# opaq_n3.net
KiCad netlist of a schematic drawn in EAGLE
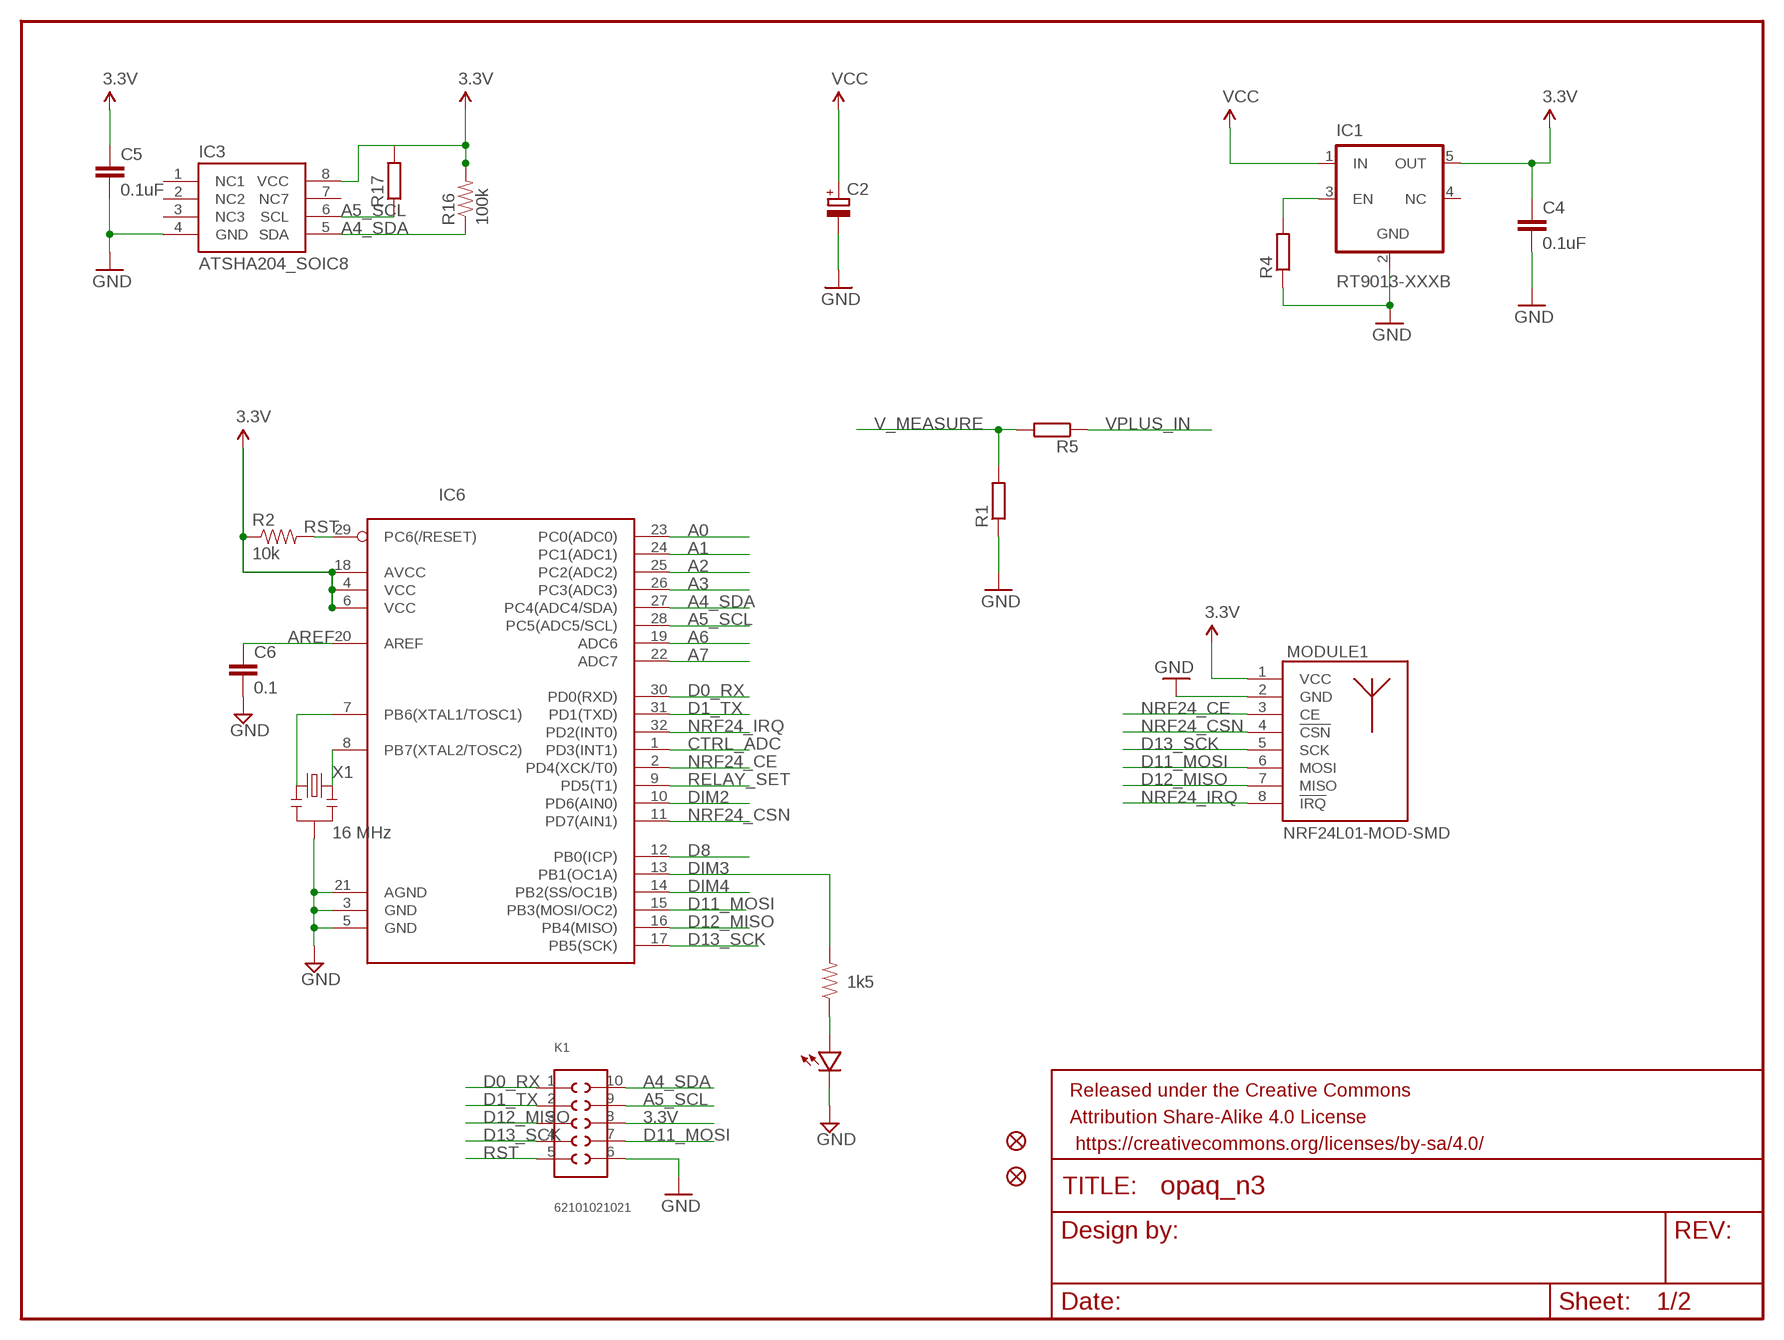
[diagram p0: schematic, sheet 1]
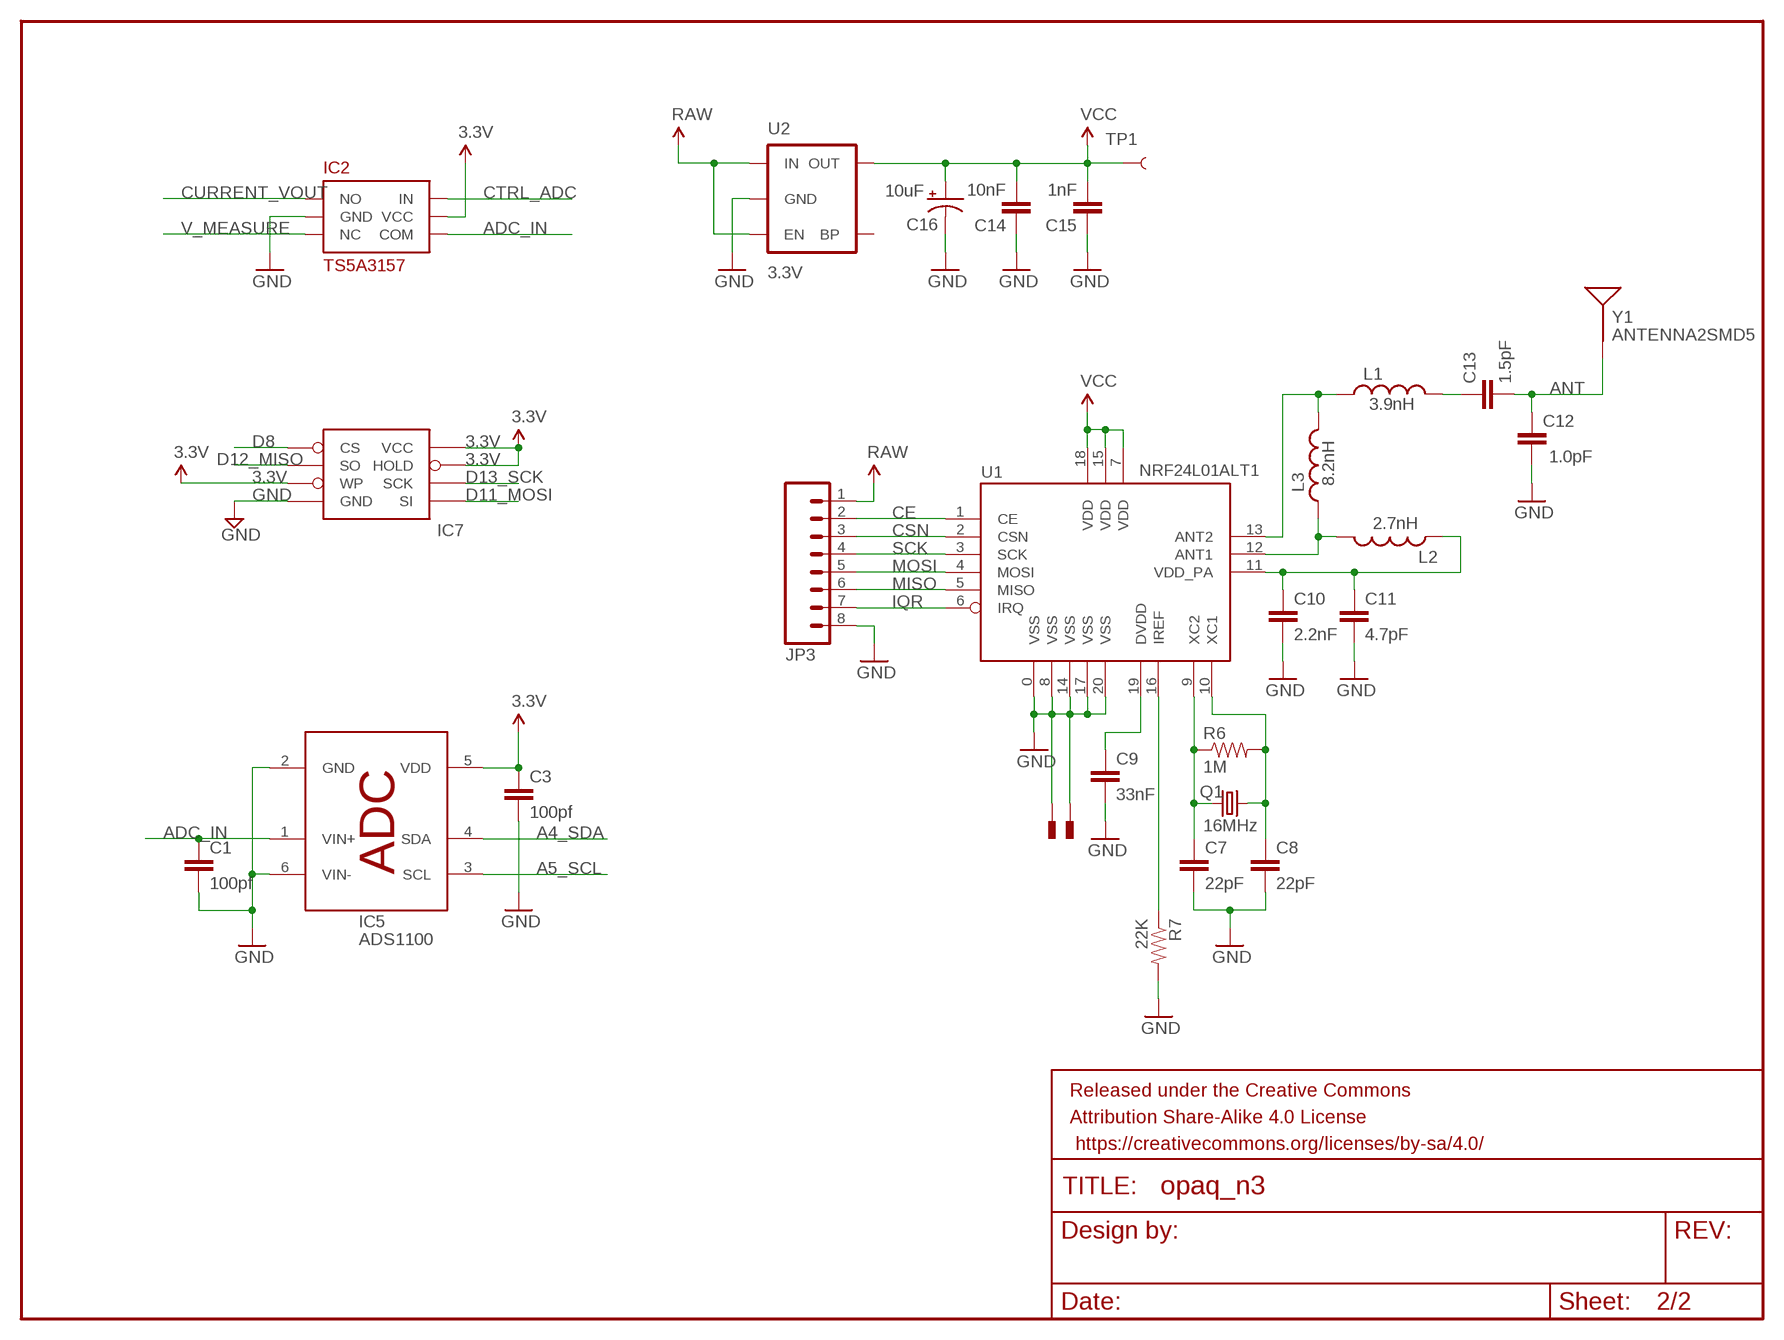
[diagram p1: schematic, sheet 2]

(export (version "E")
  (design (tool "Eeschema 10.0.6"))
  (components
    (comp (ref "C2")
      (value "CPOL-EUC/6032-28R")
      (footprint "eagle-import:C_6032-28R")
      (libsource (lib "eagle-import") (part "CPOL-EUC/6032-28R"))
    )
    (comp (ref "C4")
      (value "0.1uF")
      (footprint "eagle-import:0805")
      (libsource (lib "eagle-import") (part "SparkFun-Passives_CAP0805"))
    )
    (comp (ref "C5")
      (value "0.1uF")
      (footprint "eagle-import:0805")
      (libsource (lib "eagle-import") (part "SparkFun-Passives_CAP0805"))
    )
    (comp (ref "C6")
      (value "0.1")
      (footprint "eagle-import:0603-CAP")
      (libsource (lib "eagle-import") (part "CAP0603-CAP"))
    )
    (comp (ref "DIM")
      (value "LED0603")
      (footprint "eagle-import:0603-LED")
      (libsource (lib "eagle-import") (part "LED0603"))
    )
    (comp (ref "FRAME1")
      (value "FRAME-LETTER")
      (footprint "eagle-import:CREATIVE_COMMONS")
      (libsource (lib "eagle-import") (part "FRAME-LETTER"))
    )
    (comp (ref "IC1")
      (value "RT9013-XXXB")
      (footprint "eagle-import:SOT23-5")
      (libsource (lib "eagle-import") (part "RT9013-XXXB"))
    )
    (comp (ref "IC3")
      (value "ATSHA204_SOIC8")
      (footprint "eagle-import:SOIC8")
      (libsource (lib "eagle-import") (part "ATSHA204_SOIC8"))
    )
    (comp (ref "IC6")
      (value "ATMega-328")
      (footprint "eagle-import:MLF32")
      (libsource (lib "eagle-import") (part "ATMEGA168/328MLF"))
    )
    (comp (ref "JP1")
      (value "FIDUCIAL1X2.5")
      (footprint "eagle-import:FIDUCIAL-1X2.5")
      (libsource (lib "eagle-import") (part "FIDUCIAL1X2.5"))
    )
    (comp (ref "JP2")
      (value "FIDUCIAL1X2.5")
      (footprint "eagle-import:FIDUCIAL-1X2.5")
      (libsource (lib "eagle-import") (part "FIDUCIAL1X2.5"))
    )
    (comp (ref "K1")
      (value "62101021021")
      (footprint "eagle-import:62101021021")
      (libsource (lib "eagle-import") (part "62101021021"))
    )
    (comp (ref "MODULE1")
      (value "NRF24L01-MOD-SMD")
      (footprint "eagle-import:SMD8-MODULE")
      (libsource (lib "eagle-import") (part "NRF24L01-MOD-SMD"))
    )
    (comp (ref "R1")
      (value "R-EU_R0805")
      (footprint "eagle-import:0805")
      (libsource (lib "eagle-import") (part "R-EU_R0805"))
    )
    (comp (ref "R2")
      (value "10k")
      (footprint "eagle-import:0603-RES")
      (libsource (lib "eagle-import") (part "RESISTOR0603-RES"))
    )
    (comp (ref "R3")
      (value "1k5")
      (footprint "eagle-import:0603-RES")
      (libsource (lib "eagle-import") (part "RESISTOR0603-RES"))
    )
    (comp (ref "R4")
      (value "R-EU_R0805")
      (footprint "eagle-import:0805")
      (libsource (lib "eagle-import") (part "R-EU_R0805"))
    )
    (comp (ref "R5")
      (value "R-EU_R0805")
      (footprint "eagle-import:0805")
      (libsource (lib "eagle-import") (part "R-EU_R0805"))
    )
    (comp (ref "R16")
      (value "100k")
      (footprint "eagle-import:0805")
      (libsource (lib "eagle-import") (part "SparkFun-Passives_RESISTOR0805-RES"))
    )
    (comp (ref "R17")
      (value "R-EU_R0805")
      (footprint "eagle-import:0805")
      (libsource (lib "eagle-import") (part "R-EU_R0805"))
    )
    (comp (ref "X1")
      (value "16 MHz")
      (footprint "eagle-import:RESONATOR-SMD")
      (libsource (lib "eagle-import") (part "RESONATORSMD"))
    )
    (comp (ref "C1")
      (value "100pf")
      (footprint "eagle-import:0402-CAP")
      (libsource (lib "eagle-import") (part "SparkFun-Passives_CAP0402-CAP"))
    )
    (comp (ref "C3")
      (value "100pf")
      (footprint "eagle-import:0402-CAP")
      (libsource (lib "eagle-import") (part "SparkFun-Passives_CAP0402-CAP"))
    )
    (comp (ref "C7")
      (value "22pF")
      (footprint "eagle-import:0402-CAP")
      (libsource (lib "eagle-import") (part "SparkFun_CAP0402-CAP"))
    )
    (comp (ref "C8")
      (value "22pF")
      (footprint "eagle-import:0402-CAP")
      (libsource (lib "eagle-import") (part "SparkFun_CAP0402-CAP"))
    )
    (comp (ref "C9")
      (value "33nF")
      (footprint "eagle-import:0402-CAP")
      (libsource (lib "eagle-import") (part "SparkFun_CAP0402-CAP"))
    )
    (comp (ref "C10")
      (value "2.2nF")
      (footprint "eagle-import:0402-CAP")
      (libsource (lib "eagle-import") (part "SparkFun_CAP0402-CAP"))
    )
    (comp (ref "C11")
      (value "4.7pF")
      (footprint "eagle-import:0402-CAP")
      (libsource (lib "eagle-import") (part "SparkFun_CAP0402-CAP"))
    )
    (comp (ref "C12")
      (value "1.0pF")
      (footprint "eagle-import:0402-CAP")
      (libsource (lib "eagle-import") (part "SparkFun_CAP0402-CAP"))
    )
    (comp (ref "C13")
      (value "1.5pF")
      (footprint "eagle-import:0402-CAP")
      (libsource (lib "eagle-import") (part "SparkFun_CAP0402-CAP"))
    )
    (comp (ref "C14")
      (value "10nF")
      (footprint "eagle-import:0402-CAP")
      (libsource (lib "eagle-import") (part "SparkFun_CAP0402-CAP"))
    )
    (comp (ref "C15")
      (value "1nF")
      (footprint "eagle-import:0402-CAP")
      (libsource (lib "eagle-import") (part "SparkFun_CAP0402-CAP"))
    )
    (comp (ref "C16")
      (value "10uF")
      (footprint "eagle-import:EIA3216")
      (libsource (lib "eagle-import") (part "CAP_POL1206"))
    )
    (comp (ref "FRAME2")
      (value "FRAME-LETTERNO_PACKAGE")
      (footprint "eagle-import:DUMMY")
      (fields (field (name "DESIGNER") "Nobody"))
      (libsource (lib "eagle-import") (part "FRAME-LETTERNO_PACKAGE"))
    )
    (comp (ref "IC2")
      (value "TS5A3157")
      (footprint "eagle-import:SOT23-6")
      (libsource (lib "eagle-import") (part "TS5A3157"))
    )
    (comp (ref "IC5")
      (value "ADS1100")
      (footprint "eagle-import:SOT23-6")
      (fields (field (name "MF") "TI"))
      (libsource (lib "eagle-import") (part "ADS1100"))
    )
    (comp (ref "IC7")
      (value "AT25F512BWIDE_5.3MM")
      (footprint "eagle-import:SO08WIDE")
      (libsource (lib "eagle-import") (part "AT25F512BWIDE_5.3MM"))
    )
    (comp (ref "JP3")
      (value "M081X08")
      (footprint "eagle-import:1X08")
      (libsource (lib "eagle-import") (part "M081X08"))
    )
    (comp (ref "L1")
      (value "3.9nH")
      (footprint "eagle-import:C0402")
      (libsource (lib "eagle-import") (part "INDUCTOR0402"))
    )
    (comp (ref "L2")
      (value "2.7nH")
      (footprint "eagle-import:C0402")
      (libsource (lib "eagle-import") (part "INDUCTOR0402"))
    )
    (comp (ref "L3")
      (value "8.2nH")
      (footprint "eagle-import:C0402")
      (libsource (lib "eagle-import") (part "INDUCTOR0402"))
    )
    (comp (ref "Q1")
      (value "16MHz")
      (footprint "eagle-import:CRYSTAL-SMD-5X3")
      (libsource (lib "eagle-import") (part "CRYSTAL5X3"))
    )
    (comp (ref "R6")
      (value "1M")
      (footprint "eagle-import:0402-RES")
      (libsource (lib "eagle-import") (part "SparkFun_RESISTOR0402-RES"))
    )
    (comp (ref "R7")
      (value "22K")
      (footprint "eagle-import:0402-RES")
      (libsource (lib "eagle-import") (part "SparkFun_RESISTOR0402-RES"))
    )
    (comp (ref "TP1")
      (value "TEST-POINT3X5")
      (footprint "eagle-import:PAD.03X.05")
      (libsource (lib "eagle-import") (part "TEST-POINT3X5"))
    )
    (comp (ref "U$1")
      (value "PAD")
      (footprint "eagle-import:PAD-0.008")
      (libsource (lib "eagle-import") (part "PAD"))
    )
    (comp (ref "U$4")
      (value "PAD")
      (footprint "eagle-import:PAD-0.008")
      (libsource (lib "eagle-import") (part "PAD"))
    )
    (comp (ref "U1")
      (value "NRF24L01ALT1")
      (footprint "eagle-import:QFN20_ALT1")
      (libsource (lib "eagle-import") (part "NRF24L01ALT1"))
    )
    (comp (ref "U2")
      (value "3.3V")
      (footprint "eagle-import:SOT23-5")
      (libsource (lib "eagle-import") (part "V_REG_LDOSMD"))
    )
    (comp (ref "Y1")
      (value "ANTENNA2SMD5")
      (footprint "eagle-import:ANTENNA-CHIP5")
      (libsource (lib "eagle-import") (part "ANTENNA2SMD5"))
    )
  )
  (nets
    (net (code "1") (name "3.3V") (class "Default")
      (node (ref "C3") (pin "1") (pinfunction "1_1") (pintype "passive"))
      (node (ref "C4") (pin "1") (pinfunction "1_1") (pintype "passive"))
      (node (ref "C5") (pin "1") (pinfunction "1_1") (pintype "passive"))
      (node (ref "IC1") (pin "5") (pinfunction "OUT_5") (pintype "passive"))
      (node (ref "IC2") (pin "5") (pinfunction "VCC_5") (pintype "bidirectional"))
      (node (ref "IC3") (pin "8") (pinfunction "VCC_8") (pintype "power_in"))
      (node (ref "IC5") (pin "5") (pinfunction "VDD_5") (pintype "power_in"))
      (node (ref "IC6") (pin "18") (pinfunction "AVCC_18") (pintype "bidirectional"))
      (node (ref "IC6") (pin "4") (pinfunction "VCC_4") (pintype "bidirectional"))
      (node (ref "IC6") (pin "6") (pinfunction "VCC_6") (pintype "bidirectional"))
      (node (ref "IC7") (pin "3") (pinfunction "WP_3") (pintype "bidirectional"))
      (node (ref "IC7") (pin "7") (pinfunction "HOLD_7") (pintype "bidirectional"))
      (node (ref "IC7") (pin "8") (pinfunction "VCC_8") (pintype "bidirectional"))
      (node (ref "K1") (pin "8") (pinfunction "8_8") (pintype "passive"))
      (node (ref "MODULE1") (pin "1") (pinfunction "VCC_1") (pintype "power_in"))
      (node (ref "R16") (pin "2") (pinfunction "2_2") (pintype "passive"))
      (node (ref "R17") (pin "2") (pinfunction "2_2") (pintype "passive"))
      (node (ref "R2") (pin "1") (pinfunction "1_1") (pintype "passive"))
    )
    (net (code "2") (name "A0") (class "Default")
      (node (ref "IC6") (pin "23") (pinfunction "PC0(ADC0)_23") (pintype "bidirectional"))
    )
    (net (code "3") (name "A1") (class "Default")
      (node (ref "IC6") (pin "24") (pinfunction "PC1(ADC1)_24") (pintype "bidirectional"))
    )
    (net (code "4") (name "A2") (class "Default")
      (node (ref "IC6") (pin "25") (pinfunction "PC2(ADC2)_25") (pintype "bidirectional"))
    )
    (net (code "5") (name "A3") (class "Default")
      (node (ref "IC6") (pin "26") (pinfunction "PC3(ADC3)_26") (pintype "bidirectional"))
    )
    (net (code "6") (name "A4_SDA") (class "Default")
      (node (ref "IC3") (pin "5") (pinfunction "SDA_5") (pintype "bidirectional"))
      (node (ref "IC5") (pin "4") (pinfunction "SDA_4") (pintype "bidirectional"))
      (node (ref "IC6") (pin "27") (pinfunction "PC4(ADC4/SDA)_27") (pintype "bidirectional"))
      (node (ref "K1") (pin "10") (pinfunction "10_10") (pintype "passive"))
      (node (ref "R16") (pin "1") (pinfunction "1_1") (pintype "passive"))
    )
    (net (code "7") (name "A5_SCL") (class "Default")
      (node (ref "IC3") (pin "6") (pinfunction "SCL_6") (pintype "bidirectional"))
      (node (ref "IC5") (pin "3") (pinfunction "SCL_3") (pintype "input"))
      (node (ref "IC6") (pin "28") (pinfunction "PC5(ADC5/SCL)_28") (pintype "bidirectional"))
      (node (ref "K1") (pin "9") (pinfunction "9_9") (pintype "passive"))
      (node (ref "R17") (pin "1") (pinfunction "1_1") (pintype "passive"))
    )
    (net (code "8") (name "A6") (class "Default")
      (node (ref "IC6") (pin "19") (pinfunction "ADC6_19") (pintype "bidirectional"))
    )
    (net (code "9") (name "A7") (class "Default")
      (node (ref "IC6") (pin "22") (pinfunction "ADC7_22") (pintype "bidirectional"))
    )
    (net (code "10") (name "ADC_IN") (class "Default")
      (node (ref "C1") (pin "1") (pinfunction "1_1") (pintype "passive"))
      (node (ref "IC2") (pin "4") (pinfunction "COM_4") (pintype "bidirectional"))
      (node (ref "IC5") (pin "1") (pinfunction "VIN+_1") (pintype "input"))
    )
    (net (code "11") (name "ANT") (class "Default")
      (node (ref "C12") (pin "2") (pinfunction "2_2") (pintype "passive"))
      (node (ref "C13") (pin "2") (pinfunction "2_2") (pintype "passive"))
      (node (ref "Y1") (pin "FEED") (pinfunction "SIGNAL_FEED") (pintype "bidirectional"))
    )
    (net (code "12") (name "AREF") (class "Default")
      (node (ref "C6") (pin "1") (pinfunction "1_1") (pintype "passive"))
      (node (ref "IC6") (pin "20") (pinfunction "AREF_20") (pintype "bidirectional"))
    )
    (net (code "13") (name "CE") (class "Default")
      (node (ref "JP3") (pin "2") (pinfunction "2_2") (pintype "passive"))
      (node (ref "U1") (pin "1") (pinfunction "CE_1") (pintype "input"))
    )
    (net (code "14") (name "CSN") (class "Default")
      (node (ref "JP3") (pin "3") (pinfunction "3_3") (pintype "passive"))
      (node (ref "U1") (pin "2") (pinfunction "CSN_2") (pintype "input"))
    )
    (net (code "15") (name "CTRL_ADC") (class "Default")
      (node (ref "IC2") (pin "6") (pinfunction "IN_6") (pintype "bidirectional"))
      (node (ref "IC6") (pin "1") (pinfunction "PD3(INT1)_1") (pintype "bidirectional"))
    )
    (net (code "16") (name "CURRENT_VOUT") (class "Default")
      (node (ref "IC2") (pin "1") (pinfunction "NO_1") (pintype "bidirectional"))
    )
    (net (code "17") (name "D0_RX") (class "Default")
      (node (ref "IC6") (pin "30") (pinfunction "PD0(RXD)_30") (pintype "bidirectional"))
      (node (ref "K1") (pin "1") (pinfunction "1_1") (pintype "passive"))
    )
    (net (code "18") (name "D1_TX") (class "Default")
      (node (ref "IC6") (pin "31") (pinfunction "PD1(TXD)_31") (pintype "bidirectional"))
      (node (ref "K1") (pin "2") (pinfunction "2_2") (pintype "passive"))
    )
    (net (code "19") (name "D8") (class "Default")
      (node (ref "IC6") (pin "12") (pinfunction "PB0(ICP)_12") (pintype "bidirectional"))
      (node (ref "IC7") (pin "1") (pinfunction "CS_1") (pintype "bidirectional"))
    )
    (net (code "20") (name "D11_MOSI") (class "Default")
      (node (ref "IC6") (pin "15") (pinfunction "PB3(MOSI/OC2)_15") (pintype "bidirectional"))
      (node (ref "IC7") (pin "5") (pinfunction "SI_5") (pintype "bidirectional"))
      (node (ref "K1") (pin "7") (pinfunction "7_7") (pintype "passive"))
      (node (ref "MODULE1") (pin "6") (pinfunction "MOSI_6") (pintype "input"))
    )
    (net (code "21") (name "D12_MISO") (class "Default")
      (node (ref "IC6") (pin "16") (pinfunction "PB4(MISO)_16") (pintype "bidirectional"))
      (node (ref "IC7") (pin "2") (pinfunction "SO_2") (pintype "bidirectional"))
      (node (ref "K1") (pin "3") (pinfunction "3_3") (pintype "passive"))
      (node (ref "MODULE1") (pin "7") (pinfunction "MISO_7") (pintype "output"))
    )
    (net (code "22") (name "D13_SCK") (class "Default")
      (node (ref "IC6") (pin "17") (pinfunction "PB5(SCK)_17") (pintype "bidirectional"))
      (node (ref "IC7") (pin "6") (pinfunction "SCK_6") (pintype "bidirectional"))
      (node (ref "K1") (pin "4") (pinfunction "4_4") (pintype "passive"))
      (node (ref "MODULE1") (pin "5") (pinfunction "SCK_5") (pintype "input"))
    )
    (net (code "23") (name "DIM2") (class "Default")
      (node (ref "IC6") (pin "10") (pinfunction "PD6(AIN0)_10") (pintype "bidirectional"))
    )
    (net (code "24") (name "DIM3") (class "Default")
      (node (ref "IC6") (pin "13") (pinfunction "PB1(OC1A)_13") (pintype "bidirectional"))
      (node (ref "R3") (pin "2") (pinfunction "2_2") (pintype "passive"))
    )
    (net (code "25") (name "DIM4") (class "Default")
      (node (ref "IC6") (pin "14") (pinfunction "PB2(SS/OC1B)_14") (pintype "bidirectional"))
    )
    (net (code "26") (name "GND") (class "Default")
      (node (ref "C1") (pin "2") (pinfunction "2_2") (pintype "passive"))
      (node (ref "C10") (pin "2") (pinfunction "2_2") (pintype "passive"))
      (node (ref "C11") (pin "2") (pinfunction "2_2") (pintype "passive"))
      (node (ref "C12") (pin "1") (pinfunction "1_1") (pintype "passive"))
      (node (ref "C14") (pin "1") (pinfunction "1_1") (pintype "passive"))
      (node (ref "C15") (pin "1") (pinfunction "1_1") (pintype "passive"))
      (node (ref "C16") (pin "C") (pinfunction "-_C") (pintype "passive"))
      (node (ref "C2") (pin "-") (pinfunction "-_-") (pintype "passive"))
      (node (ref "C3") (pin "2") (pinfunction "2_2") (pintype "passive"))
      (node (ref "C4") (pin "2") (pinfunction "2_2") (pintype "passive"))
      (node (ref "C5") (pin "2") (pinfunction "2_2") (pintype "passive"))
      (node (ref "C6") (pin "2") (pinfunction "2_2") (pintype "passive"))
      (node (ref "C7") (pin "2") (pinfunction "2_2") (pintype "passive"))
      (node (ref "C8") (pin "2") (pinfunction "2_2") (pintype "passive"))
      (node (ref "C9") (pin "2") (pinfunction "2_2") (pintype "passive"))
      (node (ref "DIM") (pin "MINUS") (pinfunction "MINUS_MINUS") (pintype "passive"))
      (node (ref "IC1") (pin "2") (pinfunction "GND_2") (pintype "power_in"))
      (node (ref "IC2") (pin "2") (pinfunction "GND_2") (pintype "bidirectional"))
      (node (ref "IC3") (pin "4") (pinfunction "GND_4") (pintype "power_in"))
      (node (ref "IC5") (pin "2") (pinfunction "GND_2") (pintype "power_in"))
      (node (ref "IC5") (pin "6") (pinfunction "VIN-_6") (pintype "input"))
      (node (ref "IC6") (pin "21") (pinfunction "AGND_21") (pintype "bidirectional"))
      (node (ref "IC6") (pin "3") (pinfunction "GND_3") (pintype "bidirectional"))
      (node (ref "IC6") (pin "5") (pinfunction "GND_5") (pintype "bidirectional"))
      (node (ref "IC7") (pin "4") (pinfunction "GND_4") (pintype "bidirectional"))
      (node (ref "JP3") (pin "8") (pinfunction "8_8") (pintype "passive"))
      (node (ref "K1") (pin "6") (pinfunction "6_6") (pintype "passive"))
      (node (ref "MODULE1") (pin "2") (pinfunction "GND_2") (pintype "power_in"))
      (node (ref "R1") (pin "1") (pinfunction "1_1") (pintype "passive"))
      (node (ref "R4") (pin "1") (pinfunction "1_1") (pintype "passive"))
      (node (ref "R7") (pin "2") (pinfunction "2_2") (pintype "passive"))
      (node (ref "U$1") (pin "P$1") (pinfunction "P$1_P$1") (pintype "bidirectional"))
      (node (ref "U$4") (pin "P$1") (pinfunction "P$1_P$1") (pintype "bidirectional"))
      (node (ref "U1") (pin "0") (pinfunction "VSS_0") (pintype "power_in"))
      (node (ref "U1") (pin "14") (pinfunction "VSS_14") (pintype "power_in"))
      (node (ref "U1") (pin "17") (pinfunction "VSS_17") (pintype "power_in"))
      (node (ref "U1") (pin "20") (pinfunction "VSS_20") (pintype "power_in"))
      (node (ref "U1") (pin "8") (pinfunction "VSS_8") (pintype "power_in"))
      (node (ref "U2") (pin "2") (pinfunction "GND_2") (pintype "input"))
      (node (ref "X1") (pin "2") (pinfunction "2_2") (pintype "passive"))
    )
    (net (code "27") (name "IQR") (class "Default")
      (node (ref "JP3") (pin "7") (pinfunction "7_7") (pintype "passive"))
      (node (ref "U1") (pin "6") (pinfunction "IRQ_6") (pintype "output"))
    )
    (net (code "28") (name "MISO") (class "Default")
      (node (ref "JP3") (pin "6") (pinfunction "6_6") (pintype "passive"))
      (node (ref "U1") (pin "5") (pinfunction "MISO_5") (pintype "output"))
    )
    (net (code "29") (name "MOSI") (class "Default")
      (node (ref "JP3") (pin "5") (pinfunction "5_5") (pintype "passive"))
      (node (ref "U1") (pin "4") (pinfunction "MOSI_4") (pintype "input"))
    )
    (net (code "30") (name "NRF24_CE") (class "Default")
      (node (ref "IC6") (pin "2") (pinfunction "PD4(XCK/T0)_2") (pintype "bidirectional"))
      (node (ref "MODULE1") (pin "3") (pinfunction "CE_3") (pintype "input"))
    )
    (net (code "31") (name "NRF24_CSN") (class "Default")
      (node (ref "IC6") (pin "11") (pinfunction "PD7(AIN1)_11") (pintype "bidirectional"))
      (node (ref "MODULE1") (pin "4") (pinfunction "~{CSN}_4") (pintype "input"))
    )
    (net (code "32") (name "NRF24_IRQ") (class "Default")
      (node (ref "IC6") (pin "32") (pinfunction "PD2(INT0)_32") (pintype "bidirectional"))
      (node (ref "MODULE1") (pin "8") (pinfunction "~{IRQ}_8") (pintype "open_collector"))
    )
    (net (code "33") (name "Net-(C13-Pad1)") (class "Default")
      (node (ref "C13") (pin "1") (pinfunction "1_1") (pintype "passive"))
      (node (ref "L1") (pin "2") (pinfunction "2_2") (pintype "passive"))
    )
    (net (code "34") (name "Net-(DIM-PadPLUS)") (class "Default")
      (node (ref "DIM") (pin "PLUS") (pinfunction "PLUS_PLUS") (pintype "passive"))
      (node (ref "R3") (pin "1") (pinfunction "1_1") (pintype "passive"))
    )
    (net (code "35") (name "Net-(IC1-EN)") (class "Default")
      (node (ref "IC1") (pin "3") (pinfunction "EN_3") (pintype "input"))
      (node (ref "R4") (pin "2") (pinfunction "2_2") (pintype "passive"))
    )
    (net (code "36") (name "Net-(IC6-PB6(XTAL1{slash}TOSC1))") (class "Default")
      (node (ref "IC6") (pin "7") (pinfunction "PB6(XTAL1/TOSC1)_7") (pintype "bidirectional"))
      (node (ref "X1") (pin "1") (pinfunction "1_1") (pintype "passive"))
    )
    (net (code "37") (name "Net-(IC6-PB7(XTAL2{slash}TOSC2))") (class "Default")
      (node (ref "IC6") (pin "8") (pinfunction "PB7(XTAL2/TOSC2)_8") (pintype "bidirectional"))
      (node (ref "X1") (pin "3") (pinfunction "3_3") (pintype "passive"))
    )
    (net (code "38") (name "Net-(Q1-2)") (class "Default")
      (node (ref "C8") (pin "1") (pinfunction "1_1") (pintype "passive"))
      (node (ref "Q1") (pin "3") (pinfunction "2_3") (pintype "passive"))
      (node (ref "R6") (pin "2") (pinfunction "2_2") (pintype "passive"))
      (node (ref "U1") (pin "10") (pinfunction "XC1_10") (pintype "input"))
    )
    (net (code "39") (name "Net-(U1-ANT1)") (class "Default")
      (node (ref "L2") (pin "2") (pinfunction "2_2") (pintype "passive"))
      (node (ref "L3") (pin "1") (pinfunction "1_1") (pintype "passive"))
      (node (ref "U1") (pin "12") (pinfunction "ANT1_12") (pintype "output"))
    )
    (net (code "40") (name "Net-(U1-ANT2)") (class "Default")
      (node (ref "L1") (pin "1") (pinfunction "1_1") (pintype "passive"))
      (node (ref "L3") (pin "2") (pinfunction "2_2") (pintype "passive"))
      (node (ref "U1") (pin "13") (pinfunction "ANT2_13") (pintype "output"))
    )
    (net (code "41") (name "Net-(U1-DVDD)") (class "Default")
      (node (ref "C9") (pin "1") (pinfunction "1_1") (pintype "passive"))
      (node (ref "U1") (pin "19") (pinfunction "DVDD_19") (pintype "power_in"))
    )
    (net (code "42") (name "Net-(U1-IREF)") (class "Default")
      (node (ref "R7") (pin "1") (pinfunction "1_1") (pintype "passive"))
      (node (ref "U1") (pin "16") (pinfunction "IREF_16") (pintype "input"))
    )
    (net (code "43") (name "Net-(U1-VDD_PA)") (class "Default")
      (node (ref "C10") (pin "1") (pinfunction "1_1") (pintype "passive"))
      (node (ref "C11") (pin "1") (pinfunction "1_1") (pintype "passive"))
      (node (ref "L2") (pin "1") (pinfunction "1_1") (pintype "passive"))
      (node (ref "U1") (pin "11") (pinfunction "VDD_PA_11") (pintype "power_in"))
    )
    (net (code "44") (name "Net-(U1-XC2)") (class "Default")
      (node (ref "C7") (pin "1") (pinfunction "1_1") (pintype "passive"))
      (node (ref "Q1") (pin "1") (pinfunction "1_1") (pintype "passive"))
      (node (ref "R6") (pin "1") (pinfunction "1_1") (pintype "passive"))
      (node (ref "U1") (pin "9") (pinfunction "XC2_9") (pintype "input"))
    )
    (net (code "45") (name "RAW") (class "Default")
      (node (ref "JP3") (pin "1") (pinfunction "1_1") (pintype "passive"))
      (node (ref "U2") (pin "1") (pinfunction "IN_1") (pintype "input"))
      (node (ref "U2") (pin "3") (pinfunction "EN_3") (pintype "input"))
    )
    (net (code "46") (name "RELAY_SET") (class "Default")
      (node (ref "IC6") (pin "9") (pinfunction "PD5(T1)_9") (pintype "bidirectional"))
    )
    (net (code "47") (name "RST") (class "Default")
      (node (ref "IC6") (pin "29") (pinfunction "PC6(/RESET)_29") (pintype "bidirectional"))
      (node (ref "K1") (pin "5") (pinfunction "5_5") (pintype "passive"))
      (node (ref "R2") (pin "2") (pinfunction "2_2") (pintype "passive"))
    )
    (net (code "48") (name "SCK") (class "Default")
      (node (ref "JP3") (pin "4") (pinfunction "4_4") (pintype "passive"))
      (node (ref "U1") (pin "3") (pinfunction "SCK_3") (pintype "input"))
    )
    (net (code "49") (name "VCC") (class "Default")
      (node (ref "C14") (pin "2") (pinfunction "2_2") (pintype "passive"))
      (node (ref "C15") (pin "2") (pinfunction "2_2") (pintype "passive"))
      (node (ref "C16") (pin "A") (pinfunction "+_A") (pintype "passive"))
      (node (ref "C2") (pin "+") (pinfunction "+_+") (pintype "passive"))
      (node (ref "IC1") (pin "1") (pinfunction "IN_1") (pintype "input"))
      (node (ref "TP1") (pin "P$1") (pinfunction "1_P$1") (pintype "bidirectional"))
      (node (ref "U1") (pin "15") (pinfunction "VDD_15") (pintype "power_in"))
      (node (ref "U1") (pin "18") (pinfunction "VDD_18") (pintype "power_in"))
      (node (ref "U1") (pin "7") (pinfunction "VDD_7") (pintype "power_in"))
      (node (ref "U2") (pin "5") (pinfunction "OUT_5") (pintype "passive"))
    )
    (net (code "50") (name "VPLUS_IN") (class "Default")
      (node (ref "R5") (pin "1") (pinfunction "1_1") (pintype "passive"))
    )
    (net (code "51") (name "V_MEASURE") (class "Default")
      (node (ref "IC2") (pin "3") (pinfunction "NC_3") (pintype "bidirectional"))
      (node (ref "R1") (pin "2") (pinfunction "2_2") (pintype "passive"))
      (node (ref "R5") (pin "2") (pinfunction "2_2") (pintype "passive"))
    )
    (net (code "52") (name "unconnected-(IC1-NC-Pad4)") (class "Default")
      (node (ref "IC1") (pin "4") (pinfunction "NC_4") (pintype "no_connect"))
    )
    (net (code "53") (name "unconnected-(IC3-NC1-Pad1)") (class "Default")
      (node (ref "IC3") (pin "1") (pinfunction "NC1_1") (pintype "no_connect"))
    )
    (net (code "54") (name "unconnected-(IC3-NC2-Pad2)") (class "Default")
      (node (ref "IC3") (pin "2") (pinfunction "NC2_2") (pintype "no_connect"))
    )
    (net (code "55") (name "unconnected-(IC3-NC3-Pad3)") (class "Default")
      (node (ref "IC3") (pin "3") (pinfunction "NC3_3") (pintype "no_connect"))
    )
    (net (code "56") (name "unconnected-(IC3-NC7-Pad7)") (class "Default")
      (node (ref "IC3") (pin "7") (pinfunction "NC7_7") (pintype "no_connect"))
    )
    (net (code "57") (name "unconnected-(U2-BP-Pad4)") (class "Default")
      (node (ref "U2") (pin "4") (pinfunction "BP_4") (pintype "input"))
    )
  )
)
